# Auction_Single_RevB_Final_Schematic.net
KiCad netlist of a schematic drawn in EAGLE
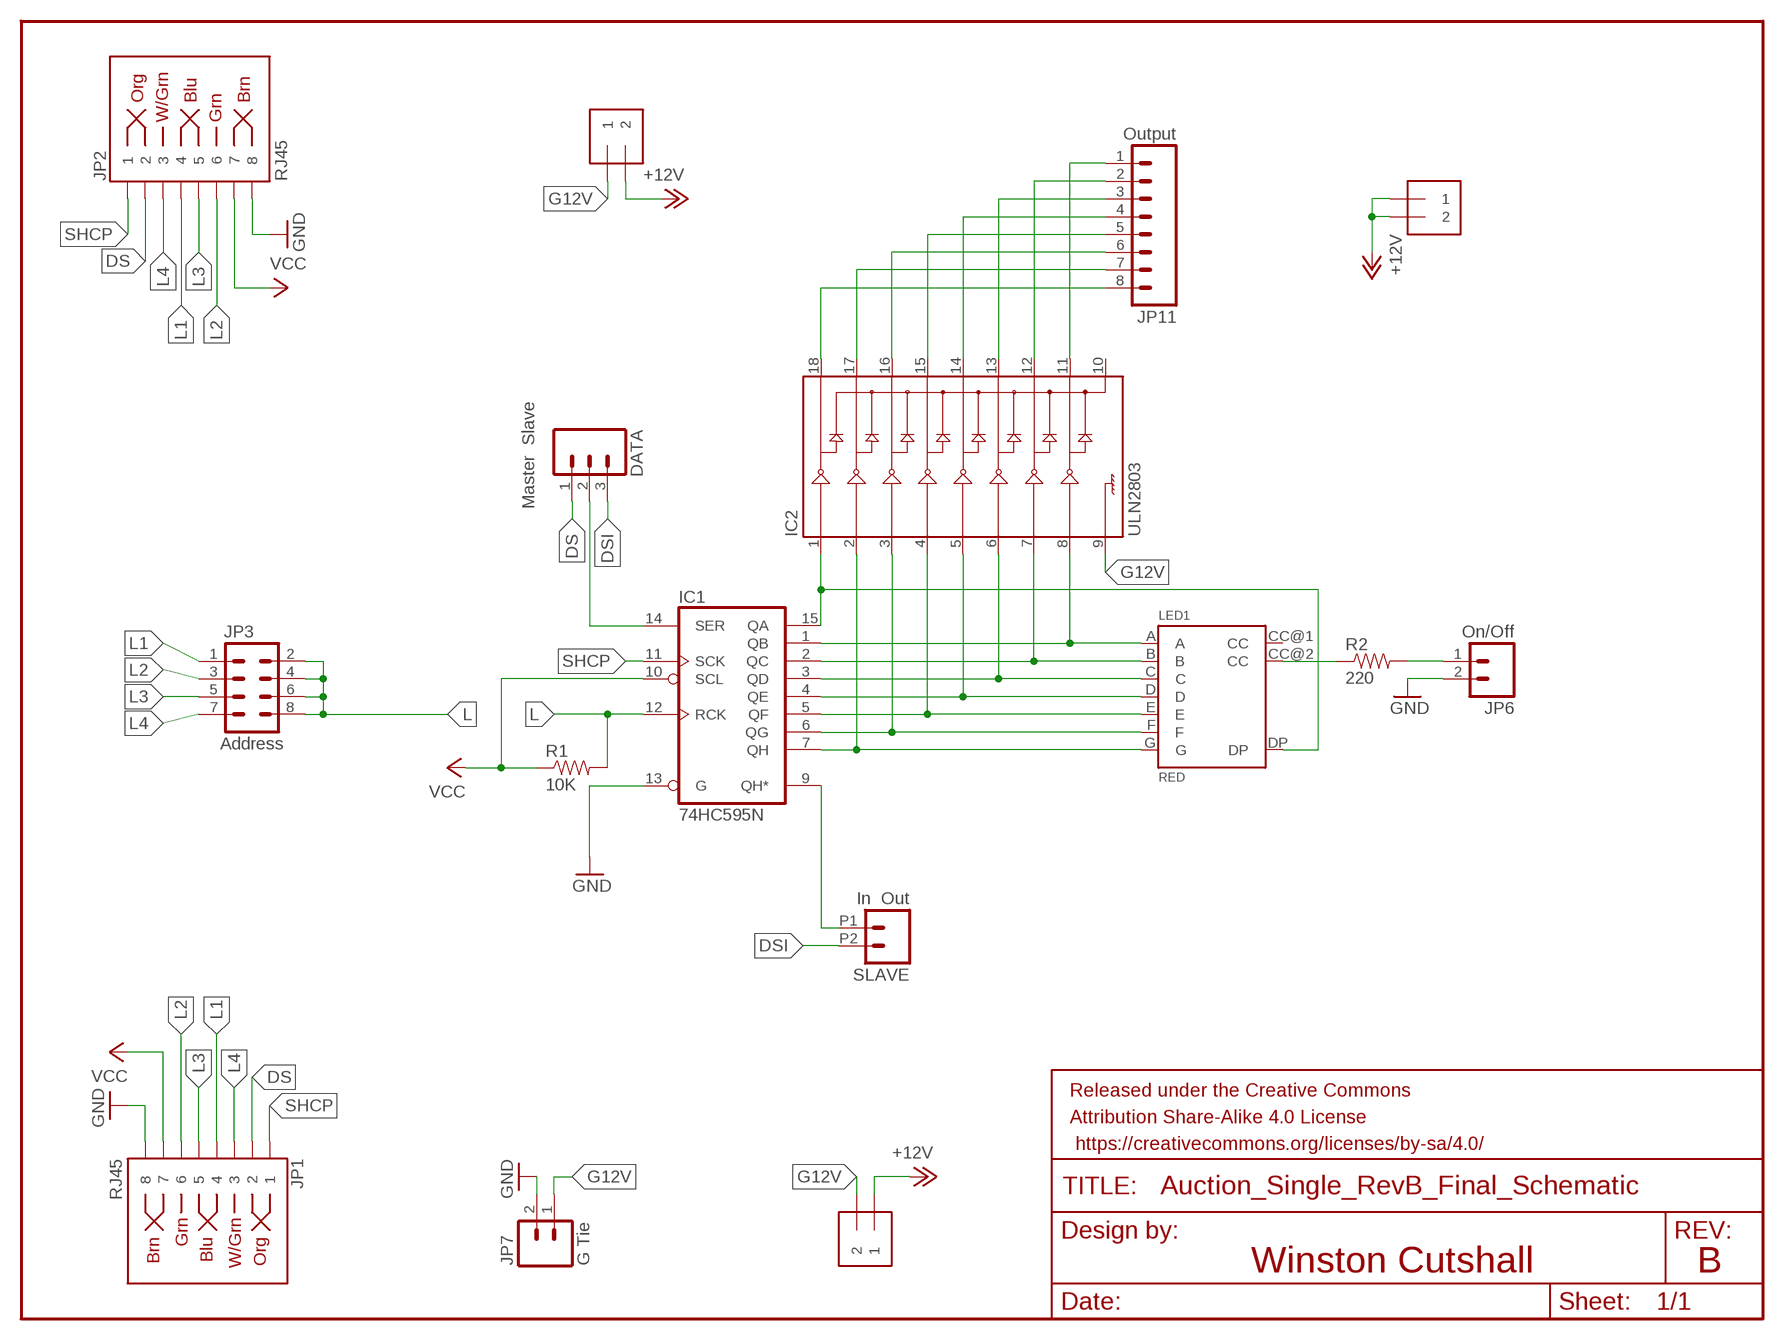
[diagram p0: schematic, sheet 1]

(export (version "E")
  (design (tool "Eeschema 10.0.6"))
  (components
    (comp (ref "DATA")
      (value "Master Slave")
      (footprint "eagle-import:1X03")
      (fields (field (name "MPN") "2211S-03G"))
      (libsource (lib "eagle-import") (part "M03PTH"))
    )
    (comp (ref "FRAME1")
      (value "FRAME-LETTER")
      (footprint "eagle-import:CREATIVE_COMMONS")
      (libsource (lib "eagle-import") (part "FRAME-LETTER"))
    )
    (comp (ref "IC1")
      (value "74HC595N")
      (footprint "eagle-import:DIL16")
      (fields (field (name "MF") "TEXAS INSTRUMENTS") (field (name "MPN") "SN74HC595N"))
      (libsource (lib "eagle-import") (part "74595NHC"))
    )
    (comp (ref "IC2")
      (value "ULN2803")
      (footprint "eagle-import:DIL18")
      (fields (field (name "MF") "Arrow Electronics") (field (name "MPN") "ULN2803A"))
      (libsource (lib "eagle-import") (part "ULN2803DIP"))
    )
    (comp (ref "JP1")
      (value "RJ45")
      (footprint "eagle-import:RJ45-8")
      (fields (field (name "MPN") "54602-908LF"))
      (libsource (lib "eagle-import") (part "RJ45-8PTH"))
    )
    (comp (ref "JP2")
      (value "RJ45")
      (footprint "eagle-import:RJ45-8")
      (fields (field (name "MPN") "54602-908LF"))
      (libsource (lib "eagle-import") (part "RJ45-8PTH"))
    )
    (comp (ref "JP3")
      (value "Address")
      (footprint "eagle-import:2X4")
      (fields (field (name "MPN") "M20-9980446"))
      (libsource (lib "eagle-import") (part "M04X2"))
    )
    (comp (ref "JP6")
      (value "On/Off")
      (footprint "eagle-import:1X02")
      (fields (field (name "MPN") "2211S-02G"))
      (libsource (lib "eagle-import") (part "M02PTH"))
    )
    (comp (ref "JP7")
      (value "G Tie")
      (footprint "eagle-import:1X02")
      (fields (field (name "MPN") "2211S-02G"))
      (libsource (lib "eagle-import") (part "M02PTH"))
    )
    (comp (ref "JP8")
      (value "1X2-3.5MM")
      (footprint "eagle-import:1X2-3.5MM")
      (fields (field (name "MPN") "1776275-2"))
      (libsource (lib "eagle-import") (part "1X2-3.5MM"))
    )
    (comp (ref "JP9")
      (value "1X2-3.5MM")
      (footprint "eagle-import:1X2-3.5MM")
      (fields (field (name "MPN") "1776275-2"))
      (libsource (lib "eagle-import") (part "1X2-3.5MM"))
    )
    (comp (ref "JP10")
      (value "1X2-3.5MM")
      (footprint "eagle-import:1X2-3.5MM")
      (fields (field (name "MPN") "1776275-2"))
      (libsource (lib "eagle-import") (part "1X2-3.5MM"))
    )
    (comp (ref "JP11")
      (value "Output")
      (footprint "eagle-import:SCREWTERMINAL-3.5MM-8")
      (fields (field (name "MPN") "20020327-C081B01LF"))
      (libsource (lib "eagle-import") (part "M083.5MM-8"))
    )
    (comp (ref "LED1")
      (value "RED")
      (footprint "eagle-import:HDSP-C3X3")
      (libsource (lib "eagle-import") (part "HDSP-C3X3"))
    )
    (comp (ref "R1")
      (value "10K")
      (footprint "eagle-import:AXIAL-0.3EZ")
      (fields (field (name "MF") "FARNELL") (field (name "MPN") "MCF 0.25W 10K"))
      (libsource (lib "eagle-import") (part "RESISTOREZ"))
    )
    (comp (ref "R2")
      (value "220")
      (footprint "eagle-import:AXIAL-0.3EZ")
      (fields (field (name "MF") "FARNELL") (field (name "MPN") "MCF 0.25W 220R"))
      (libsource (lib "eagle-import") (part "RESISTOREZ"))
    )
    (comp (ref "SLAVE")
      (value "In Out")
      (footprint "eagle-import:1X02_2.54_SCREWTERM")
      (fields (field (name "MF") "TYCO ELECTRONICS") (field (name "MPN") "282834-2"))
      (libsource (lib "eagle-import") (part "M022.54MM_SCREWTERM"))
    )
  )
  (nets
    (net (code "1") (name "+12V") (class "Default")
      (node (ref "JP10") (pin "1") (pinfunction "1_1") (pintype "passive"))
      (node (ref "JP10") (pin "2") (pinfunction "2_2") (pintype "passive"))
      (node (ref "JP8") (pin "1") (pinfunction "1_1") (pintype "passive"))
      (node (ref "JP9") (pin "2") (pinfunction "2_2") (pintype "passive"))
    )
    (net (code "2") (name "DS") (class "Default")
      (node (ref "DATA") (pin "1") (pinfunction "1_1") (pintype "passive"))
      (node (ref "JP1") (pin "2") (pinfunction "2_2") (pintype "bidirectional"))
      (node (ref "JP2") (pin "2") (pinfunction "2_2") (pintype "bidirectional"))
    )
    (net (code "3") (name "DSI") (class "Default")
      (node (ref "DATA") (pin "3") (pinfunction "3_3") (pintype "passive"))
      (node (ref "SLAVE") (pin "P2") (pinfunction "2_P2") (pintype "passive"))
    )
    (net (code "4") (name "G12V") (class "Default")
      (node (ref "IC2") (pin "9") (pinfunction "9_9") (pintype "bidirectional"))
      (node (ref "JP7") (pin "1") (pinfunction "1_1") (pintype "passive"))
      (node (ref "JP8") (pin "2") (pinfunction "2_2") (pintype "passive"))
      (node (ref "JP9") (pin "1") (pinfunction "1_1") (pintype "passive"))
    )
    (net (code "5") (name "GND") (class "Default")
      (node (ref "IC1") (pin "13") (pinfunction "G_13") (pintype "input"))
      (node (ref "JP1") (pin "8") (pinfunction "8_8") (pintype "bidirectional"))
      (node (ref "JP2") (pin "8") (pinfunction "8_8") (pintype "bidirectional"))
      (node (ref "JP6") (pin "2") (pinfunction "2_2") (pintype "passive"))
      (node (ref "JP7") (pin "2") (pinfunction "2_2") (pintype "passive"))
    )
    (net (code "6") (name "L") (class "Default")
      (node (ref "IC1") (pin "12") (pinfunction "RCK_12") (pintype "input"))
      (node (ref "JP3") (pin "2") (pinfunction "2_2") (pintype "passive"))
      (node (ref "JP3") (pin "4") (pinfunction "4_4") (pintype "passive"))
      (node (ref "JP3") (pin "6") (pinfunction "6_6") (pintype "passive"))
      (node (ref "JP3") (pin "8") (pinfunction "8_8") (pintype "passive"))
      (node (ref "R1") (pin "P$2") (pinfunction "2_P$2") (pintype "passive"))
    )
    (net (code "7") (name "L1") (class "Default")
      (node (ref "JP1") (pin "4") (pinfunction "4_4") (pintype "bidirectional"))
      (node (ref "JP2") (pin "4") (pinfunction "4_4") (pintype "bidirectional"))
      (node (ref "JP3") (pin "1") (pinfunction "1_1") (pintype "passive"))
    )
    (net (code "8") (name "L2") (class "Default")
      (node (ref "JP1") (pin "6") (pinfunction "6_6") (pintype "bidirectional"))
      (node (ref "JP2") (pin "6") (pinfunction "6_6") (pintype "bidirectional"))
      (node (ref "JP3") (pin "3") (pinfunction "3_3") (pintype "passive"))
    )
    (net (code "9") (name "L3") (class "Default")
      (node (ref "JP1") (pin "5") (pinfunction "5_5") (pintype "bidirectional"))
      (node (ref "JP2") (pin "5") (pinfunction "5_5") (pintype "bidirectional"))
      (node (ref "JP3") (pin "5") (pinfunction "5_5") (pintype "passive"))
    )
    (net (code "10") (name "L4") (class "Default")
      (node (ref "JP1") (pin "3") (pinfunction "3_3") (pintype "bidirectional"))
      (node (ref "JP2") (pin "3") (pinfunction "3_3") (pintype "bidirectional"))
      (node (ref "JP3") (pin "7") (pinfunction "7_7") (pintype "passive"))
    )
    (net (code "11") (name "Net-(IC1A-QA)") (class "Default")
      (node (ref "IC1") (pin "15") (pinfunction "QA_15") (pintype "tri_state"))
      (node (ref "IC2") (pin "1") (pinfunction "1_1") (pintype "bidirectional"))
      (node (ref "LED1") (pin "DP") (pinfunction "DP_DP") (pintype "bidirectional"))
    )
    (net (code "12") (name "Net-(IC1A-QB)") (class "Default")
      (node (ref "IC1") (pin "1") (pinfunction "QB_1") (pintype "tri_state"))
      (node (ref "IC2") (pin "8") (pinfunction "8_8") (pintype "bidirectional"))
      (node (ref "LED1") (pin "A") (pinfunction "A_A") (pintype "bidirectional"))
    )
    (net (code "13") (name "Net-(IC1A-QC)") (class "Default")
      (node (ref "IC1") (pin "2") (pinfunction "QC_2") (pintype "tri_state"))
      (node (ref "IC2") (pin "7") (pinfunction "7_7") (pintype "bidirectional"))
      (node (ref "LED1") (pin "B") (pinfunction "B_B") (pintype "bidirectional"))
    )
    (net (code "14") (name "Net-(IC1A-QD)") (class "Default")
      (node (ref "IC1") (pin "3") (pinfunction "QD_3") (pintype "tri_state"))
      (node (ref "IC2") (pin "6") (pinfunction "6_6") (pintype "bidirectional"))
      (node (ref "LED1") (pin "C") (pinfunction "C_C") (pintype "bidirectional"))
    )
    (net (code "15") (name "Net-(IC1A-QE)") (class "Default")
      (node (ref "IC1") (pin "4") (pinfunction "QE_4") (pintype "tri_state"))
      (node (ref "IC2") (pin "5") (pinfunction "5_5") (pintype "bidirectional"))
      (node (ref "LED1") (pin "D") (pinfunction "D_D") (pintype "bidirectional"))
    )
    (net (code "16") (name "Net-(IC1A-QF)") (class "Default")
      (node (ref "IC1") (pin "5") (pinfunction "QF_5") (pintype "tri_state"))
      (node (ref "IC2") (pin "4") (pinfunction "4_4") (pintype "bidirectional"))
      (node (ref "LED1") (pin "E") (pinfunction "E_E") (pintype "bidirectional"))
    )
    (net (code "17") (name "Net-(IC1A-QG)") (class "Default")
      (node (ref "IC1") (pin "6") (pinfunction "QG_6") (pintype "tri_state"))
      (node (ref "IC2") (pin "3") (pinfunction "3_3") (pintype "bidirectional"))
      (node (ref "LED1") (pin "F") (pinfunction "F_F") (pintype "bidirectional"))
    )
    (net (code "18") (name "Net-(IC1A-QH)") (class "Default")
      (node (ref "IC1") (pin "7") (pinfunction "QH_7") (pintype "tri_state"))
      (node (ref "IC2") (pin "2") (pinfunction "2_2") (pintype "bidirectional"))
      (node (ref "LED1") (pin "G") (pinfunction "G_G") (pintype "bidirectional"))
    )
    (net (code "19") (name "Net-(IC1A-QH*)") (class "Default")
      (node (ref "IC1") (pin "9") (pinfunction "QH*_9") (pintype "tri_state"))
      (node (ref "SLAVE") (pin "P1") (pinfunction "1_P1") (pintype "passive"))
    )
    (net (code "20") (name "Net-(IC1A-SER)") (class "Default")
      (node (ref "DATA") (pin "2") (pinfunction "2_2") (pintype "passive"))
      (node (ref "IC1") (pin "14") (pinfunction "SER_14") (pintype "input"))
    )
    (net (code "21") (name "Net-(IC2-Pad11)") (class "Default")
      (node (ref "IC2") (pin "11") (pinfunction "11_11") (pintype "bidirectional"))
      (node (ref "JP11") (pin "1") (pinfunction "1_1") (pintype "passive"))
    )
    (net (code "22") (name "Net-(IC2-Pad12)") (class "Default")
      (node (ref "IC2") (pin "12") (pinfunction "12_12") (pintype "bidirectional"))
      (node (ref "JP11") (pin "2") (pinfunction "2_2") (pintype "passive"))
    )
    (net (code "23") (name "Net-(IC2-Pad13)") (class "Default")
      (node (ref "IC2") (pin "13") (pinfunction "13_13") (pintype "bidirectional"))
      (node (ref "JP11") (pin "3") (pinfunction "3_3") (pintype "passive"))
    )
    (net (code "24") (name "Net-(IC2-Pad14)") (class "Default")
      (node (ref "IC2") (pin "14") (pinfunction "14_14") (pintype "bidirectional"))
      (node (ref "JP11") (pin "4") (pinfunction "4_4") (pintype "passive"))
    )
    (net (code "25") (name "Net-(IC2-Pad15)") (class "Default")
      (node (ref "IC2") (pin "15") (pinfunction "15_15") (pintype "bidirectional"))
      (node (ref "JP11") (pin "5") (pinfunction "5_5") (pintype "passive"))
    )
    (net (code "26") (name "Net-(IC2-Pad16)") (class "Default")
      (node (ref "IC2") (pin "16") (pinfunction "16_16") (pintype "bidirectional"))
      (node (ref "JP11") (pin "6") (pinfunction "6_6") (pintype "passive"))
    )
    (net (code "27") (name "Net-(IC2-Pad17)") (class "Default")
      (node (ref "IC2") (pin "17") (pinfunction "17_17") (pintype "bidirectional"))
      (node (ref "JP11") (pin "7") (pinfunction "7_7") (pintype "passive"))
    )
    (net (code "28") (name "Net-(IC2-Pad18)") (class "Default")
      (node (ref "IC2") (pin "18") (pinfunction "18_18") (pintype "bidirectional"))
      (node (ref "JP11") (pin "8") (pinfunction "8_8") (pintype "passive"))
    )
    (net (code "29") (name "Net-(R2-1)") (class "Default")
      (node (ref "LED1") (pin "CC@2") (pinfunction "CC_CC@2") (pintype "bidirectional"))
      (node (ref "R2") (pin "P$1") (pinfunction "1_P$1") (pintype "passive"))
    )
    (net (code "30") (name "Net-(R2-2)") (class "Default")
      (node (ref "JP6") (pin "1") (pinfunction "1_1") (pintype "passive"))
      (node (ref "R2") (pin "P$2") (pinfunction "2_P$2") (pintype "passive"))
    )
    (net (code "31") (name "SHCP") (class "Default")
      (node (ref "IC1") (pin "11") (pinfunction "SCK_11") (pintype "input"))
      (node (ref "JP1") (pin "1") (pinfunction "1_1") (pintype "bidirectional"))
      (node (ref "JP2") (pin "1") (pinfunction "1_1") (pintype "bidirectional"))
    )
    (net (code "32") (name "VCC") (class "Default")
      (node (ref "IC1") (pin "10") (pinfunction "SCL_10") (pintype "input"))
      (node (ref "JP1") (pin "7") (pinfunction "7_7") (pintype "bidirectional"))
      (node (ref "JP2") (pin "7") (pinfunction "7_7") (pintype "bidirectional"))
      (node (ref "R1") (pin "P$1") (pinfunction "1_P$1") (pintype "passive"))
    )
    (net (code "33") (name "unconnected-(IC2-Pad10)") (class "Default")
      (node (ref "IC2") (pin "10") (pinfunction "10_10") (pintype "bidirectional"))
    )
    (net (code "34") (name "unconnected-(LED1-CC-PadCC@1)") (class "Default")
      (node (ref "LED1") (pin "CC@1") (pinfunction "CC_CC@1") (pintype "bidirectional"))
    )
  )
)
